# Tracking-Car.net
KiCad netlist of a schematic drawn in EasyEDA Pro
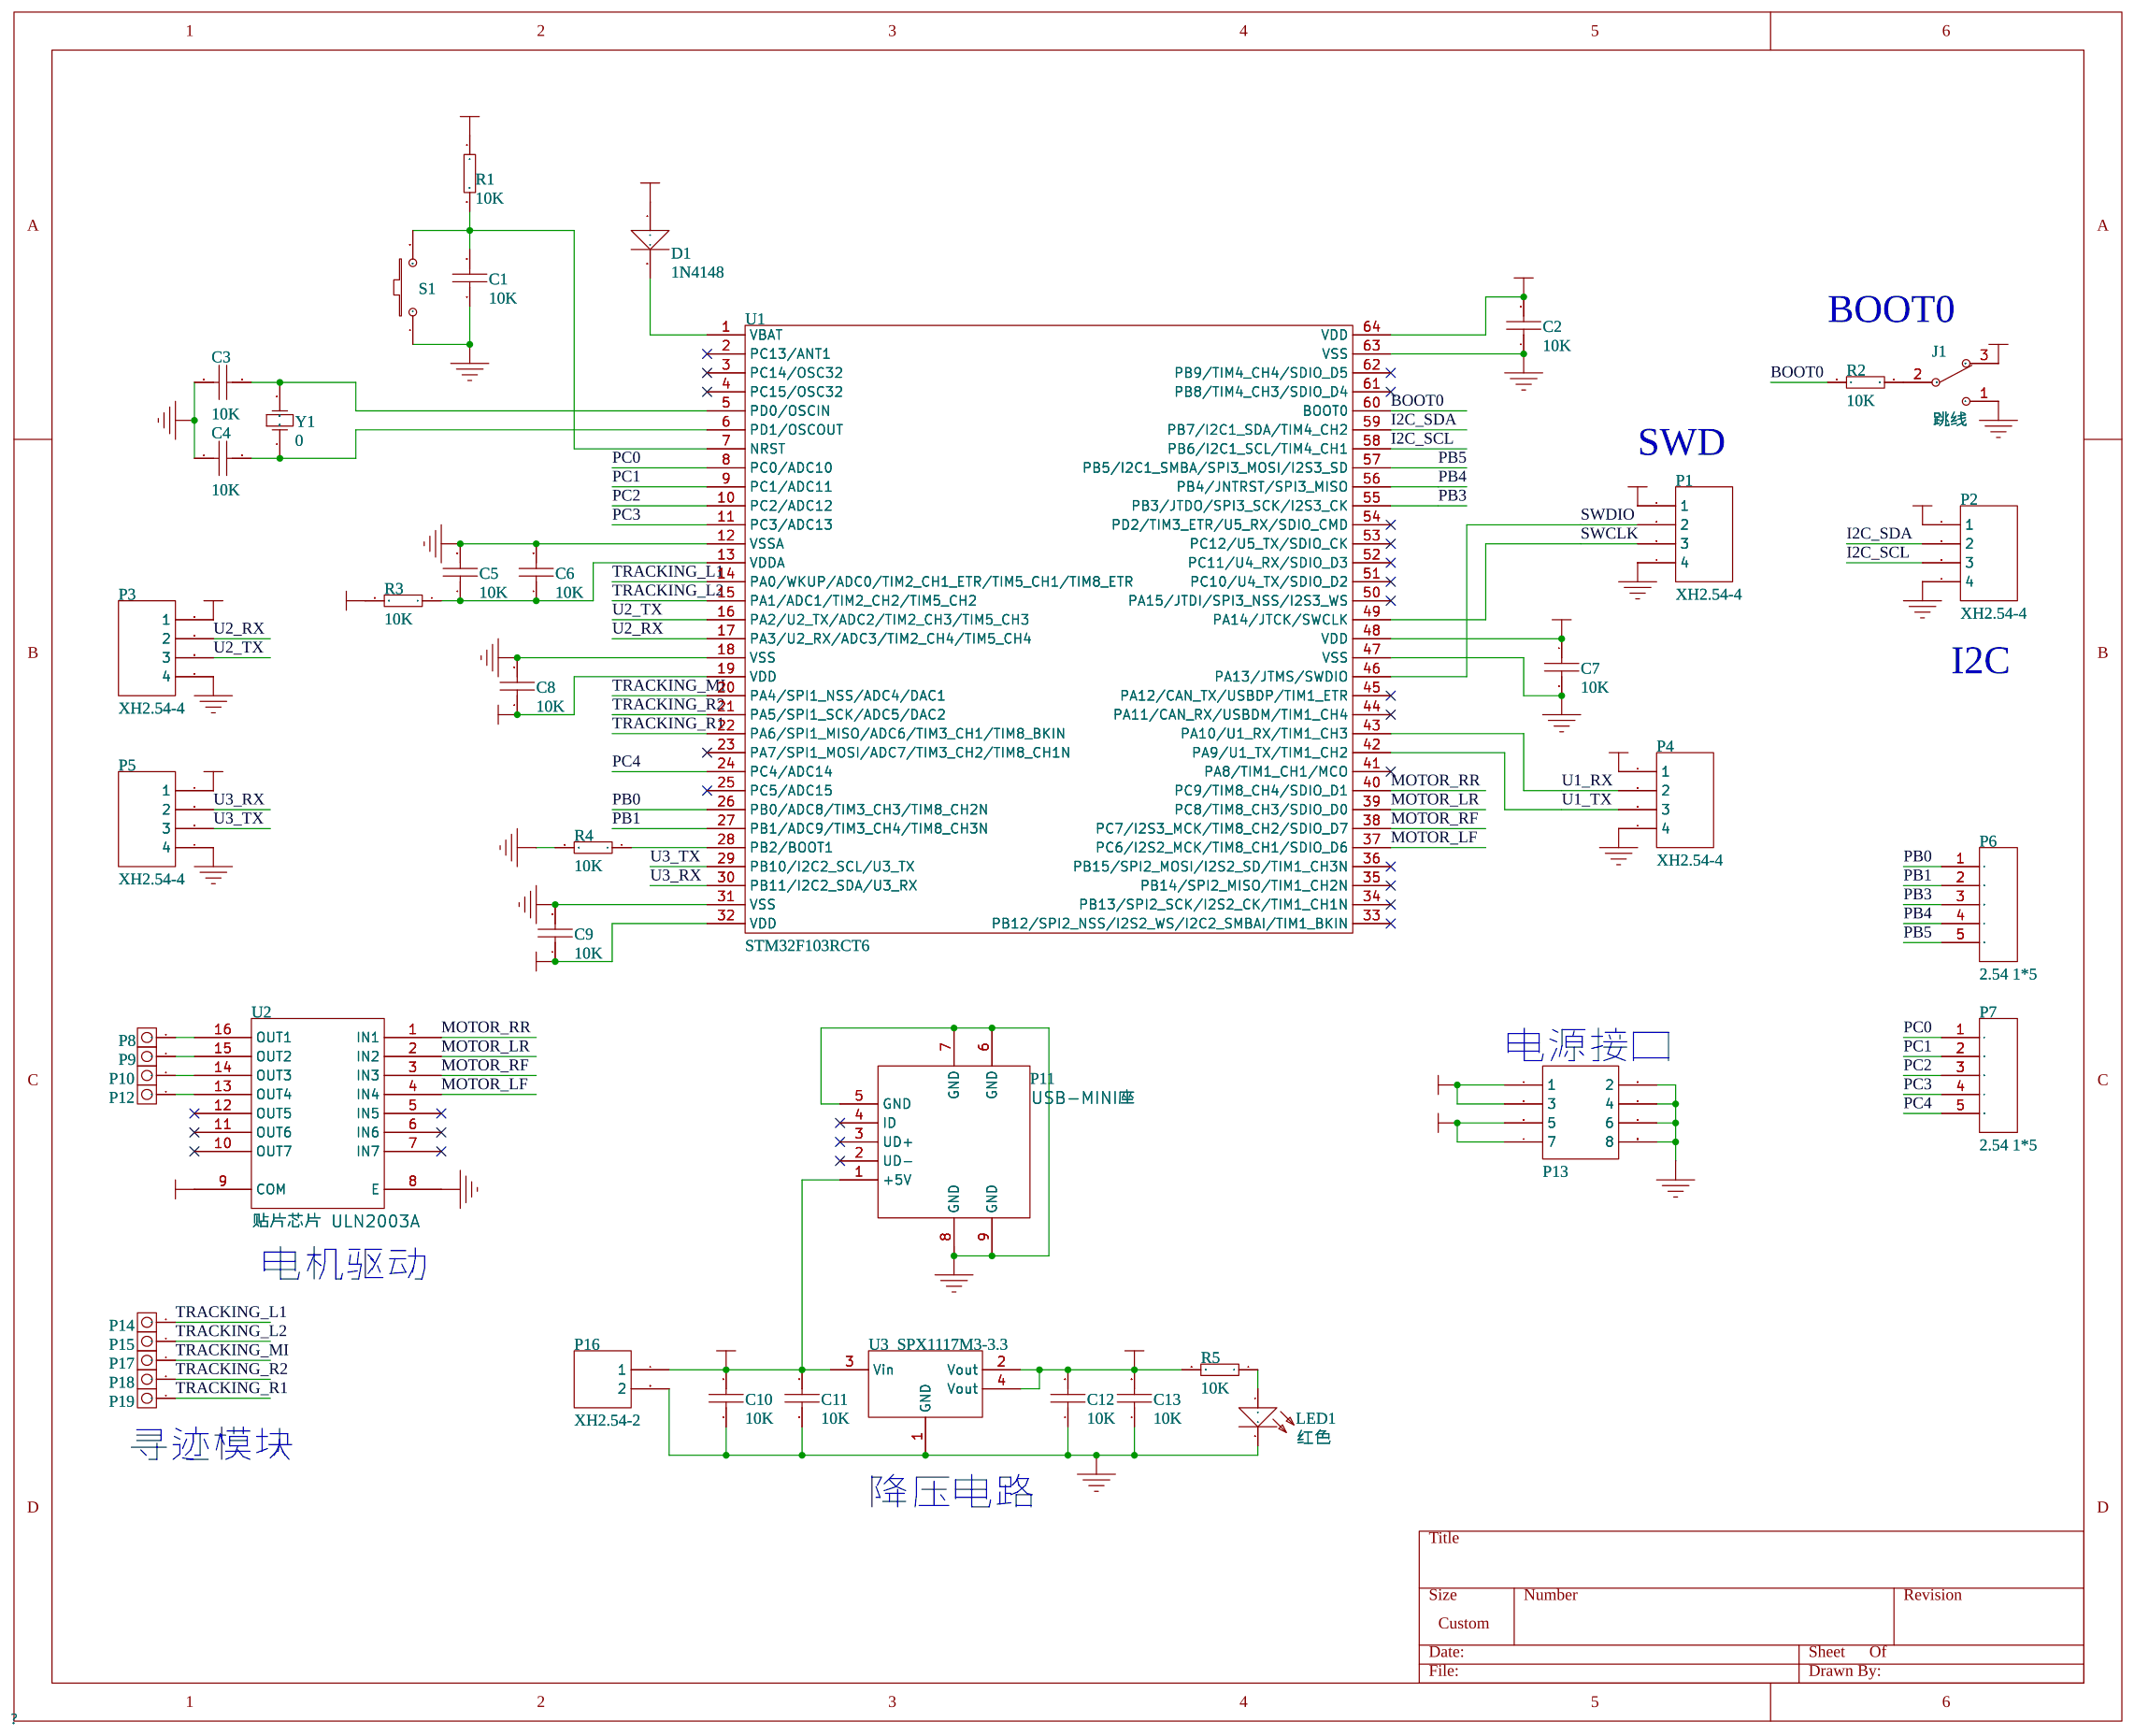
[diagram p0: schematic sheet]

(export (version "E")
  (design (tool "Eeschema 10.0.6"))
  (components
    (comp (ref "C1")
      (value "10K")
      (footprint "easyedapro:0805")
      (libsource (lib "easyedapro") (part "电容 贴片 0805"))
    )
    (comp (ref "C2")
      (value "10K")
      (footprint "easyedapro:0805")
      (libsource (lib "easyedapro") (part "电容 贴片 0805"))
    )
    (comp (ref "C3")
      (value "10K")
      (footprint "easyedapro:0805")
      (libsource (lib "easyedapro") (part "电容 贴片 0805"))
    )
    (comp (ref "C4")
      (value "10K")
      (footprint "easyedapro:0805")
      (libsource (lib "easyedapro") (part "电容 贴片 0805"))
    )
    (comp (ref "C5")
      (value "10K")
      (footprint "easyedapro:0805")
      (libsource (lib "easyedapro") (part "电容 贴片 0805"))
    )
    (comp (ref "C6")
      (value "10K")
      (footprint "easyedapro:0805")
      (libsource (lib "easyedapro") (part "电容 贴片 0805"))
    )
    (comp (ref "C7")
      (value "10K")
      (footprint "easyedapro:0805")
      (libsource (lib "easyedapro") (part "电容 贴片 0805"))
    )
    (comp (ref "C8")
      (value "10K")
      (footprint "easyedapro:0805")
      (libsource (lib "easyedapro") (part "电容 贴片 0805"))
    )
    (comp (ref "C9")
      (value "10K")
      (footprint "easyedapro:0805")
      (libsource (lib "easyedapro") (part "电容 贴片 0805"))
    )
    (comp (ref "C10")
      (value "10K")
      (footprint "easyedapro:0805")
      (libsource (lib "easyedapro") (part "电容 贴片 0805"))
    )
    (comp (ref "C11")
      (value "10K")
      (footprint "easyedapro:0805")
      (libsource (lib "easyedapro") (part "电容 贴片 0805"))
    )
    (comp (ref "C12")
      (value "10K")
      (footprint "easyedapro:0805")
      (libsource (lib "easyedapro") (part "电容 贴片 0805"))
    )
    (comp (ref "C13")
      (value "10K")
      (footprint "easyedapro:0805")
      (libsource (lib "easyedapro") (part "电容 贴片 0805"))
    )
    (comp (ref "D1")
      (value "1N4148")
      (footprint "easyedapro:Ƭ IN4148")
      (libsource (lib "easyedapro") (part "二极管 贴片 1N4148"))
    )
    (comp (ref "J1")
      (value "跳线")
      (footprint "easyedapro:Ų 2.54 1*3")
      (libsource (lib "easyedapro") (part "联结件 跳线端子 2.54-3"))
    )
    (comp (ref "LED1")
      (value "红色")
      (footprint "easyedapro:LED0805")
      (libsource (lib "easyedapro") (part "二极管 贴片发光 0805"))
    )
    (comp (ref "P1")
      (value "XH2.54-4")
      (footprint "easyedapro:VH2.54_4")
      (libsource (lib "easyedapro") (part "联结件 XH2.54-4"))
    )
    (comp (ref "P2")
      (value "XH2.54-4")
      (footprint "easyedapro:VH2.54_4")
      (libsource (lib "easyedapro") (part "联结件 XH2.54-4"))
    )
    (comp (ref "P3")
      (value "XH2.54-4")
      (footprint "easyedapro:VH2.54_4")
      (libsource (lib "easyedapro") (part "联结件 XH2.54-4"))
    )
    (comp (ref "P4")
      (value "XH2.54-4")
      (footprint "easyedapro:VH2.54_4")
      (libsource (lib "easyedapro") (part "联结件 XH2.54-4"))
    )
    (comp (ref "P5")
      (value "XH2.54-4")
      (footprint "easyedapro:VH2.54_4")
      (libsource (lib "easyedapro") (part "联结件 XH2.54-4"))
    )
    (comp (ref "P6")
      (value "2.54 1*5")
      (footprint "easyedapro:Ų 2.54 1*5")
      (libsource (lib "easyedapro") (part "联结件 单排插针 2.54 1*5"))
    )
    (comp (ref "P7")
      (value "2.54 1*5")
      (footprint "easyedapro:Ų 2.54 1*5")
      (libsource (lib "easyedapro") (part "联结件 单排插针 2.54 1*5"))
    )
    (comp (ref "P8")
      (value "DZ254R-11-01-63")
      (fields (field (name "Manufacturer") "DEALON(德艺隆)"))
      (libsource (lib "easyedapro") (part "焊盘"))
    )
    (comp (ref "P9")
      (value "DZ254R-11-01-63")
      (fields (field (name "Manufacturer") "DEALON(德艺隆)"))
      (libsource (lib "easyedapro") (part "焊盘"))
    )
    (comp (ref "P10")
      (value "DZ254R-11-01-63")
      (fields (field (name "Manufacturer") "DEALON(德艺隆)"))
      (libsource (lib "easyedapro") (part "焊盘"))
    )
    (comp (ref "P11")
      (value "USB-MINI座")
      (footprint "easyedapro:USB MINI DIP")
      (libsource (lib "easyedapro") (part "联结件 USB-MINI座"))
    )
    (comp (ref "P12")
      (value "DZ254R-11-01-63")
      (fields (field (name "Manufacturer") "DEALON(德艺隆)"))
      (libsource (lib "easyedapro") (part "焊盘"))
    )
    (comp (ref "P13") (value "双排插针 2.54 2*4") (libsource (lib "easyedapro") (part "联结件 双排插针 2.54 2*4")))
    (comp (ref "P14")
      (value "DZ254R-11-01-63")
      (fields (field (name "Manufacturer") "DEALON(德艺隆)"))
      (libsource (lib "easyedapro") (part "焊盘"))
    )
    (comp (ref "P15")
      (value "DZ254R-11-01-63")
      (fields (field (name "Manufacturer") "DEALON(德艺隆)"))
      (libsource (lib "easyedapro") (part "焊盘"))
    )
    (comp (ref "P16")
      (value "XH2.54-2")
      (footprint "easyedapro:VH2.54_2")
      (libsource (lib "easyedapro") (part "联结件 XH2.54-2"))
    )
    (comp (ref "P17")
      (value "DZ254R-11-01-63")
      (fields (field (name "Manufacturer") "DEALON(德艺隆)"))
      (libsource (lib "easyedapro") (part "焊盘"))
    )
    (comp (ref "P18")
      (value "DZ254R-11-01-63")
      (fields (field (name "Manufacturer") "DEALON(德艺隆)"))
      (libsource (lib "easyedapro") (part "焊盘"))
    )
    (comp (ref "P19")
      (value "DZ254R-11-01-63")
      (fields (field (name "Manufacturer") "DEALON(德艺隆)"))
      (libsource (lib "easyedapro") (part "焊盘"))
    )
    (comp (ref "R1")
      (value "10K")
      (footprint "easyedapro:autoName_08bedda2daa9906a")
      (libsource (lib "easyedapro") (part "电阻 贴片 0805"))
    )
    (comp (ref "R2")
      (value "10K")
      (footprint "easyedapro:autoName_08bedda2daa9906a")
      (libsource (lib "easyedapro") (part "电阻 贴片 0805"))
    )
    (comp (ref "R3")
      (value "10K")
      (footprint "easyedapro:autoName_08bedda2daa9906a")
      (libsource (lib "easyedapro") (part "电阻 贴片 0805"))
    )
    (comp (ref "R4")
      (value "10K")
      (footprint "easyedapro:autoName_08bedda2daa9906a")
      (libsource (lib "easyedapro") (part "电阻 贴片 0805"))
    )
    (comp (ref "R5")
      (value "10K")
      (footprint "easyedapro:autoName_08bedda2daa9906a")
      (libsource (lib "easyedapro") (part "电阻 贴片 0805"))
    )
    (comp (ref "S1")
      (value "key")
      (footprint "easyedapro:ᴥ  6*3")
      (libsource (lib "easyedapro") (part "按键 轻触 3*6"))
    )
    (comp (ref "U1")
      (value "STM32F103RCT6")
      (footprint "easyedapro:LQFP64")
      (description "单片机")
      (libsource (lib "easyedapro") (part "贴片芯片 STM32F103RCT6"))
    )
    (comp (ref "U2")
      (value "贴片芯片 ULN2003A")
      (footprint "easyedapro:SOIC16")
      (libsource (lib "easyedapro") (part "贴片芯片 ULN2003A"))
    )
    (comp (ref "U3")
      (value "SPX1117M3-3.3")
      (footprint "easyedapro:SOT223")
      (description "LDO")
      (libsource (lib "easyedapro") (part "贴片芯片 SPX1117M3-3.3"))
    )
    (comp (ref "Y1")
      (value "0")
      (footprint "easyedapro:BCY-W2/E4.7")
      (libsource (lib "easyedapro") (part "晶振 直插矮"))
    )
  )
  (nets
    (net (code "1") (name "/BOOT0") (class "Default")
      (node (ref "R2") (pin "2") (pinfunction "2_2") (pintype "input"))
      (node (ref "U1") (pin "60") (pinfunction "BOOT0_60") (pintype "input"))
    )
    (net (code "2") (name "/I2C_SCL") (class "Default")
      (node (ref "P2") (pin "3") (pinfunction "3_3") (pintype "input"))
      (node (ref "U1") (pin "58") (pinfunction "PB6/I2C1_SCL/TIM4_CH1_58") (pintype "input"))
    )
    (net (code "3") (name "/I2C_SDA") (class "Default")
      (node (ref "P2") (pin "2") (pinfunction "2_2") (pintype "input"))
      (node (ref "U1") (pin "59") (pinfunction "PB7/I2C1_SDA/TIM4_CH2_59") (pintype "input"))
    )
    (net (code "4") (name "/MOTOR_LF") (class "Default")
      (node (ref "U1") (pin "37") (pinfunction "PC6/I2S2_MCK/TIM8_CH1/SDIO_D6_37") (pintype "input"))
      (node (ref "U2") (pin "4") (pinfunction "IN4_4") (pintype "input"))
    )
    (net (code "5") (name "/MOTOR_LR") (class "Default")
      (node (ref "U1") (pin "39") (pinfunction "PC8/TIM8_CH3/SDIO_D0_39") (pintype "input"))
      (node (ref "U2") (pin "2") (pinfunction "IN2_2") (pintype "input"))
    )
    (net (code "6") (name "/MOTOR_RF") (class "Default")
      (node (ref "U1") (pin "38") (pinfunction "PC7/I2S3_MCK/TIM8_CH2/SDIO_D7_38") (pintype "input"))
      (node (ref "U2") (pin "3") (pinfunction "IN3_3") (pintype "input"))
    )
    (net (code "7") (name "/MOTOR_RR") (class "Default")
      (node (ref "U1") (pin "40") (pinfunction "PC9/TIM8_CH4/SDIO_D1_40") (pintype "input"))
      (node (ref "U2") (pin "1") (pinfunction "IN1_1") (pintype "input"))
    )
    (net (code "8") (name "/PB0") (class "Default")
      (node (ref "P6") (pin "1") (pinfunction "1_1") (pintype "input"))
      (node (ref "U1") (pin "26") (pinfunction "PB0/ADC8/TIM3_CH3/TIM8_CH2N_26") (pintype "input"))
    )
    (net (code "9") (name "/PB1") (class "Default")
      (node (ref "P6") (pin "2") (pinfunction "2_2") (pintype "input"))
      (node (ref "U1") (pin "27") (pinfunction "PB1/ADC9/TIM3_CH4/TIM8_CH3N_27") (pintype "input"))
    )
    (net (code "10") (name "/PB3") (class "Default")
      (node (ref "P6") (pin "3") (pinfunction "3_3") (pintype "input"))
      (node (ref "U1") (pin "55") (pinfunction "PB3/JTDO/SPI3_SCK/I2S3_CK_55") (pintype "input"))
    )
    (net (code "11") (name "/PB4") (class "Default")
      (node (ref "P6") (pin "4") (pinfunction "4_4") (pintype "input"))
      (node (ref "U1") (pin "56") (pinfunction "PB4/JNTRST/SPI3_MISO_56") (pintype "input"))
    )
    (net (code "12") (name "/PB5") (class "Default")
      (node (ref "P6") (pin "5") (pinfunction "5_5") (pintype "input"))
      (node (ref "U1") (pin "57") (pinfunction "PB5/I2C1_SMBA/SPI3_MOSI/I2S3_SD_57") (pintype "input"))
    )
    (net (code "13") (name "/PC0") (class "Default")
      (node (ref "P7") (pin "1") (pinfunction "1_1") (pintype "input"))
      (node (ref "U1") (pin "8") (pinfunction "PC0/ADC10_8") (pintype "input"))
    )
    (net (code "14") (name "/PC1") (class "Default")
      (node (ref "P7") (pin "2") (pinfunction "2_2") (pintype "input"))
      (node (ref "U1") (pin "9") (pinfunction "PC1/ADC11_9") (pintype "input"))
    )
    (net (code "15") (name "/PC2") (class "Default")
      (node (ref "P7") (pin "3") (pinfunction "3_3") (pintype "input"))
      (node (ref "U1") (pin "10") (pinfunction "PC2/ADC12_10") (pintype "input"))
    )
    (net (code "16") (name "/PC3") (class "Default")
      (node (ref "P7") (pin "4") (pinfunction "4_4") (pintype "input"))
      (node (ref "U1") (pin "11") (pinfunction "PC3/ADC13_11") (pintype "input"))
    )
    (net (code "17") (name "/PC4") (class "Default")
      (node (ref "P7") (pin "5") (pinfunction "5_5") (pintype "input"))
      (node (ref "U1") (pin "24") (pinfunction "PC4/ADC14_24") (pintype "input"))
    )
    (net (code "18") (name "/SWCLK") (class "Default")
      (node (ref "P1") (pin "3") (pinfunction "3_3") (pintype "input"))
      (node (ref "U1") (pin "49") (pinfunction "PA14/JTCK/SWCLK_49") (pintype "input"))
    )
    (net (code "19") (name "/SWDIO") (class "Default")
      (node (ref "P1") (pin "2") (pinfunction "2_2") (pintype "input"))
      (node (ref "U1") (pin "46") (pinfunction "PA13/JTMS/SWDIO_46") (pintype "input"))
    )
    (net (code "20") (name "/TRACKING_L1") (class "Default")
      (node (ref "P14") (pin "1") (pinfunction "1_1") (pintype "input"))
      (node (ref "U1") (pin "14") (pinfunction "PA0/WKUP/ADC0/TIM2_CH1_ETR/TIM5_CH1/TIM8_ETR_14") (pintype "input"))
    )
    (net (code "21") (name "/TRACKING_L2") (class "Default")
      (node (ref "P15") (pin "1") (pinfunction "1_1") (pintype "input"))
      (node (ref "U1") (pin "15") (pinfunction "PA1/ADC1/TIM2_CH2/TIM5_CH2_15") (pintype "input"))
    )
    (net (code "22") (name "/TRACKING_MI") (class "Default")
      (node (ref "P17") (pin "1") (pinfunction "1_1") (pintype "input"))
      (node (ref "U1") (pin "20") (pinfunction "PA4/SPI1_NSS/ADC4/DAC1_20") (pintype "input"))
    )
    (net (code "23") (name "/TRACKING_R1") (class "Default")
      (node (ref "P19") (pin "1") (pinfunction "1_1") (pintype "input"))
      (node (ref "U1") (pin "22") (pinfunction "PA6/SPI1_MISO/ADC6/TIM3_CH1/TIM8_BKIN_22") (pintype "input"))
    )
    (net (code "24") (name "/TRACKING_R2") (class "Default")
      (node (ref "P18") (pin "1") (pinfunction "1_1") (pintype "input"))
      (node (ref "U1") (pin "21") (pinfunction "PA5/SPI1_SCK/ADC5/DAC2_21") (pintype "input"))
    )
    (net (code "25") (name "/U1_RX") (class "Default")
      (node (ref "P4") (pin "2") (pinfunction "2_2") (pintype "input"))
      (node (ref "U1") (pin "43") (pinfunction "PA10/U1_RX/TIM1_CH3_43") (pintype "input"))
    )
    (net (code "26") (name "/U1_TX") (class "Default")
      (node (ref "P4") (pin "3") (pinfunction "3_3") (pintype "input"))
      (node (ref "U1") (pin "42") (pinfunction "PA9/U1_TX/TIM1_CH2_42") (pintype "input"))
    )
    (net (code "27") (name "/U2_RX") (class "Default")
      (node (ref "P3") (pin "2") (pinfunction "2_2") (pintype "input"))
      (node (ref "U1") (pin "17") (pinfunction "PA3/U2_RX/ADC3/TIM2_CH4/TIM5_CH4_17") (pintype "input"))
    )
    (net (code "28") (name "/U2_TX") (class "Default")
      (node (ref "P3") (pin "3") (pinfunction "3_3") (pintype "input"))
      (node (ref "U1") (pin "16") (pinfunction "PA2/U2_TX/ADC2/TIM2_CH3/TIM5_CH3_16") (pintype "input"))
    )
    (net (code "29") (name "/U3_RX") (class "Default")
      (node (ref "P5") (pin "2") (pinfunction "2_2") (pintype "input"))
      (node (ref "U1") (pin "30") (pinfunction "PB11/I2C2_SDA/U3_RX_30") (pintype "input"))
    )
    (net (code "30") (name "/U3_TX") (class "Default")
      (node (ref "P5") (pin "3") (pinfunction "3_3") (pintype "input"))
      (node (ref "U1") (pin "29") (pinfunction "PB10/I2C2_SCL/U3_TX_29") (pintype "input"))
    )
    (net (code "31") (name "3.3V") (class "Default")
      (node (ref "C12") (pin "2") (pintype "input"))
      (node (ref "C13") (pin "2") (pintype "input"))
      (node (ref "C2") (pin "2") (pintype "input"))
      (node (ref "C7") (pin "1") (pintype "input"))
      (node (ref "C8") (pin "1") (pintype "input"))
      (node (ref "C9") (pin "1") (pintype "input"))
      (node (ref "D1") (pin "1") (pinfunction "A_1") (pintype "input"))
      (node (ref "J1") (pin "3") (pinfunction "3_3") (pintype "input"))
      (node (ref "P1") (pin "1") (pinfunction "1_1") (pintype "input"))
      (node (ref "P13") (pin "1") (pinfunction "1_1") (pintype "input"))
      (node (ref "P13") (pin "3") (pinfunction "3_3") (pintype "input"))
      (node (ref "P2") (pin "1") (pinfunction "1_1") (pintype "input"))
      (node (ref "P3") (pin "1") (pinfunction "1_1") (pintype "input"))
      (node (ref "P4") (pin "1") (pinfunction "1_1") (pintype "input"))
      (node (ref "P5") (pin "1") (pinfunction "1_1") (pintype "input"))
      (node (ref "R1") (pin "1") (pinfunction "1_1") (pintype "input"))
      (node (ref "R3") (pin "2") (pinfunction "2_2") (pintype "input"))
      (node (ref "R5") (pin "2") (pinfunction "2_2") (pintype "input"))
      (node (ref "U1") (pin "19") (pinfunction "VDD_19") (pintype "input"))
      (node (ref "U1") (pin "32") (pinfunction "VDD_32") (pintype "input"))
      (node (ref "U1") (pin "48") (pinfunction "VDD_48") (pintype "input"))
      (node (ref "U1") (pin "64") (pinfunction "VDD_64") (pintype "input"))
      (node (ref "U3") (pin "2") (pinfunction "Vout_2") (pintype "input"))
      (node (ref "U3") (pin "4") (pinfunction "Vout_4") (pintype "input"))
    )
    (net (code "32") (name "5V") (class "Default")
      (node (ref "C10") (pin "2") (pintype "input"))
      (node (ref "C11") (pin "2") (pintype "input"))
      (node (ref "P11") (pin "1") (pinfunction "+5V_1") (pintype "input"))
      (node (ref "P13") (pin "5") (pinfunction "5_5") (pintype "input"))
      (node (ref "P13") (pin "7") (pinfunction "7_7") (pintype "input"))
      (node (ref "P16") (pin "1") (pinfunction "1_1") (pintype "input"))
      (node (ref "U2") (pin "9") (pinfunction "COM_9") (pintype "input"))
      (node (ref "U3") (pin "3") (pinfunction "Vin_3") (pintype "input"))
    )
    (net (code "33") (name "GND") (class "Default")
      (node (ref "C1") (pin "1") (pintype "input"))
      (node (ref "C10") (pin "1") (pintype "input"))
      (node (ref "C11") (pin "1") (pintype "input"))
      (node (ref "C12") (pin "1") (pintype "input"))
      (node (ref "C13") (pin "1") (pintype "input"))
      (node (ref "C2") (pin "1") (pintype "input"))
      (node (ref "C3") (pin "1") (pintype "input"))
      (node (ref "C4") (pin "1") (pintype "input"))
      (node (ref "C5") (pin "2") (pintype "input"))
      (node (ref "C6") (pin "2") (pintype "input"))
      (node (ref "C7") (pin "2") (pintype "input"))
      (node (ref "C8") (pin "2") (pintype "input"))
      (node (ref "C9") (pin "2") (pintype "input"))
      (node (ref "J1") (pin "1") (pinfunction "1_1") (pintype "input"))
      (node (ref "LED1") (pin "2") (pinfunction "K_2") (pintype "input"))
      (node (ref "P1") (pin "4") (pinfunction "4_4") (pintype "input"))
      (node (ref "P11") (pin "5") (pinfunction "GND_5") (pintype "input"))
      (node (ref "P11") (pin "6") (pinfunction "GND_6") (pintype "input"))
      (node (ref "P11") (pin "7") (pinfunction "GND_7") (pintype "input"))
      (node (ref "P11") (pin "8") (pinfunction "GND_8") (pintype "input"))
      (node (ref "P11") (pin "9") (pinfunction "GND_9") (pintype "input"))
      (node (ref "P13") (pin "2") (pinfunction "2_2") (pintype "input"))
      (node (ref "P13") (pin "4") (pinfunction "4_4") (pintype "input"))
      (node (ref "P13") (pin "6") (pinfunction "6_6") (pintype "input"))
      (node (ref "P13") (pin "8") (pinfunction "8_8") (pintype "input"))
      (node (ref "P16") (pin "2") (pinfunction "2_2") (pintype "input"))
      (node (ref "P2") (pin "4") (pinfunction "4_4") (pintype "input"))
      (node (ref "P3") (pin "4") (pinfunction "4_4") (pintype "input"))
      (node (ref "P4") (pin "4") (pinfunction "4_4") (pintype "input"))
      (node (ref "P5") (pin "4") (pinfunction "4_4") (pintype "input"))
      (node (ref "R4") (pin "2") (pinfunction "2_2") (pintype "input"))
      (node (ref "S1") (pin "1") (pinfunction "1_1") (pintype "input"))
      (node (ref "U1") (pin "12") (pinfunction "VSSA_12") (pintype "input"))
      (node (ref "U1") (pin "18") (pinfunction "VSS_18") (pintype "input"))
      (node (ref "U1") (pin "31") (pinfunction "VSS_31") (pintype "input"))
      (node (ref "U1") (pin "47") (pinfunction "VSS_47") (pintype "input"))
      (node (ref "U1") (pin "63") (pinfunction "VSS_63") (pintype "input"))
      (node (ref "U2") (pin "8") (pinfunction "E_8") (pintype "input"))
      (node (ref "U3") (pin "1") (pinfunction "GND_1") (pintype "input"))
    )
    (net (code "34") (name "Net-(D1-K)") (class "Default")
      (node (ref "D1") (pin "2") (pinfunction "K_2") (pintype "input"))
      (node (ref "U1") (pin "1") (pinfunction "VBAT_1") (pintype "input"))
    )
    (net (code "35") (name "Net-(J1-Pad2)") (class "Default")
      (node (ref "J1") (pin "2") (pinfunction "2_2") (pintype "input"))
      (node (ref "R2") (pin "1") (pinfunction "1_1") (pintype "input"))
    )
    (net (code "36") (name "Net-(LED1-A)") (class "Default")
      (node (ref "LED1") (pin "1") (pinfunction "A_1") (pintype "input"))
      (node (ref "R5") (pin "1") (pinfunction "1_1") (pintype "input"))
    )
    (net (code "37") (name "Net-(U1-NRST)") (class "Default")
      (node (ref "C1") (pin "2") (pintype "input"))
      (node (ref "R1") (pin "2") (pinfunction "2_2") (pintype "input"))
      (node (ref "S1") (pin "2") (pinfunction "2_2") (pintype "input"))
      (node (ref "U1") (pin "7") (pinfunction "NRST_7") (pintype "input"))
    )
    (net (code "38") (name "Net-(U1-PB2{slash}BOOT1)") (class "Default")
      (node (ref "R4") (pin "1") (pinfunction "1_1") (pintype "input"))
      (node (ref "U1") (pin "28") (pinfunction "PB2/BOOT1_28") (pintype "input"))
    )
    (net (code "39") (name "Net-(U1-PD0{slash}OSCIN)") (class "Default")
      (node (ref "C3") (pin "2") (pintype "input"))
      (node (ref "U1") (pin "5") (pinfunction "PD0/OSCIN_5") (pintype "input"))
      (node (ref "Y1") (pin "2") (pinfunction "OSC2_2") (pintype "input"))
    )
    (net (code "40") (name "Net-(U1-PD1{slash}OSCOUT)") (class "Default")
      (node (ref "C4") (pin "2") (pintype "input"))
      (node (ref "U1") (pin "6") (pinfunction "PD1/OSCOUT_6") (pintype "input"))
      (node (ref "Y1") (pin "1") (pinfunction "OSC1_1") (pintype "input"))
    )
    (net (code "41") (name "Net-(U1-VDDA)") (class "Default")
      (node (ref "C5") (pin "1") (pintype "input"))
      (node (ref "C6") (pin "1") (pintype "input"))
      (node (ref "R3") (pin "1") (pinfunction "1_1") (pintype "input"))
      (node (ref "U1") (pin "13") (pinfunction "VDDA_13") (pintype "input"))
    )
    (net (code "42") (name "Net-(U2-OUT1)") (class "Default")
      (node (ref "P8") (pin "1") (pinfunction "1_1") (pintype "input"))
      (node (ref "U2") (pin "16") (pinfunction "OUT1_16") (pintype "input"))
    )
    (net (code "43") (name "Net-(U2-OUT2)") (class "Default")
      (node (ref "P9") (pin "1") (pinfunction "1_1") (pintype "input"))
      (node (ref "U2") (pin "15") (pinfunction "OUT2_15") (pintype "input"))
    )
    (net (code "44") (name "Net-(U2-OUT3)") (class "Default")
      (node (ref "P10") (pin "1") (pinfunction "1_1") (pintype "input"))
      (node (ref "U2") (pin "14") (pinfunction "OUT3_14") (pintype "input"))
    )
    (net (code "45") (name "Net-(U2-OUT4)") (class "Default")
      (node (ref "P12") (pin "1") (pinfunction "1_1") (pintype "input"))
      (node (ref "U2") (pin "13") (pinfunction "OUT4_13") (pintype "input"))
    )
    (net (code "46") (name "unconnected-(P11-ID-Pad4)") (class "Default")
      (node (ref "P11") (pin "4") (pinfunction "ID_4") (pintype "input+no_connect"))
    )
    (net (code "47") (name "unconnected-(P11-UD+-Pad3)") (class "Default")
      (node (ref "P11") (pin "3") (pinfunction "UD+_3") (pintype "input+no_connect"))
    )
    (net (code "48") (name "unconnected-(P11-UD--Pad2)") (class "Default")
      (node (ref "P11") (pin "2") (pinfunction "UD-_2") (pintype "input+no_connect"))
    )
    (net (code "49") (name "unconnected-(U1-PA7{slash}SPI1_MOSI{slash}ADC7{slash}TIM3_CH2{slash}TIM8_CH1N-Pad23)") (class "Default")
      (node (ref "U1") (pin "23") (pinfunction "PA7/SPI1_MOSI/ADC7/TIM3_CH2/TIM8_CH1N_23") (pintype "input+no_connect"))
    )
    (net (code "50") (name "unconnected-(U1-PA8{slash}TIM1_CH1{slash}MCO-Pad41)") (class "Default")
      (node (ref "U1") (pin "41") (pinfunction "PA8/TIM1_CH1/MCO_41") (pintype "input+no_connect"))
    )
    (net (code "51") (name "unconnected-(U1-PA11{slash}CAN_RX{slash}USBDM{slash}TIM1_CH4-Pad44)") (class "Default")
      (node (ref "U1") (pin "44") (pinfunction "PA11/CAN_RX/USBDM/TIM1_CH4_44") (pintype "input+no_connect"))
    )
    (net (code "52") (name "unconnected-(U1-PA12{slash}CAN_TX{slash}USBDP{slash}TIM1_ETR-Pad45)") (class "Default")
      (node (ref "U1") (pin "45") (pinfunction "PA12/CAN_TX/USBDP/TIM1_ETR_45") (pintype "input+no_connect"))
    )
    (net (code "53") (name "unconnected-(U1-PA15{slash}JTDI{slash}SPI3_NSS{slash}I2S3_WS-Pad50)") (class "Default")
      (node (ref "U1") (pin "50") (pinfunction "PA15/JTDI/SPI3_NSS/I2S3_WS_50") (pintype "input+no_connect"))
    )
    (net (code "54") (name "unconnected-(U1-PB8{slash}TIM4_CH3{slash}SDIO_D4-Pad61)") (class "Default")
      (node (ref "U1") (pin "61") (pinfunction "PB8/TIM4_CH3/SDIO_D4_61") (pintype "input+no_connect"))
    )
    (net (code "55") (name "unconnected-(U1-PB9{slash}TIM4_CH4{slash}SDIO_D5-Pad62)") (class "Default")
      (node (ref "U1") (pin "62") (pinfunction "PB9/TIM4_CH4/SDIO_D5_62") (pintype "input+no_connect"))
    )
    (net (code "56") (name "unconnected-(U1-PB12{slash}SPI2_NSS{slash}I2S2_WS{slash}I2C2_SMBAI{slash}TIM1_BKIN-Pad33)") (class "Default")
      (node (ref "U1") (pin "33") (pinfunction "PB12/SPI2_NSS/I2S2_WS/I2C2_SMBAI/TIM1_BKIN_33") (pintype "input+no_connect"))
    )
    (net (code "57") (name "unconnected-(U1-PB13{slash}SPI2_SCK{slash}I2S2_CK{slash}TIM1_CH1N-Pad34)") (class "Default")
      (node (ref "U1") (pin "34") (pinfunction "PB13/SPI2_SCK/I2S2_CK/TIM1_CH1N_34") (pintype "input+no_connect"))
    )
    (net (code "58") (name "unconnected-(U1-PB14{slash}SPI2_MISO{slash}TIM1_CH2N-Pad35)") (class "Default")
      (node (ref "U1") (pin "35") (pinfunction "PB14/SPI2_MISO/TIM1_CH2N_35") (pintype "input+no_connect"))
    )
    (net (code "59") (name "unconnected-(U1-PB15{slash}SPI2_MOSI{slash}I2S2_SD{slash}TIM1_CH3N-Pad36)") (class "Default")
      (node (ref "U1") (pin "36") (pinfunction "PB15/SPI2_MOSI/I2S2_SD/TIM1_CH3N_36") (pintype "input+no_connect"))
    )
    (net (code "60") (name "unconnected-(U1-PC5{slash}ADC15-Pad25)") (class "Default")
      (node (ref "U1") (pin "25") (pinfunction "PC5/ADC15_25") (pintype "input+no_connect"))
    )
    (net (code "61") (name "unconnected-(U1-PC10{slash}U4_TX{slash}SDIO_D2-Pad51)") (class "Default")
      (node (ref "U1") (pin "51") (pinfunction "PC10/U4_TX/SDIO_D2_51") (pintype "input+no_connect"))
    )
    (net (code "62") (name "unconnected-(U1-PC11{slash}U4_RX{slash}SDIO_D3-Pad52)") (class "Default")
      (node (ref "U1") (pin "52") (pinfunction "PC11/U4_RX/SDIO_D3_52") (pintype "input+no_connect"))
    )
    (net (code "63") (name "unconnected-(U1-PC12{slash}U5_TX{slash}SDIO_CK-Pad53)") (class "Default")
      (node (ref "U1") (pin "53") (pinfunction "PC12/U5_TX/SDIO_CK_53") (pintype "input+no_connect"))
    )
    (net (code "64") (name "unconnected-(U1-PC13{slash}ANT1-Pad2)") (class "Default")
      (node (ref "U1") (pin "2") (pinfunction "PC13/ANT1_2") (pintype "input+no_connect"))
    )
    (net (code "65") (name "unconnected-(U1-PC14{slash}OSC32-Pad3)") (class "Default")
      (node (ref "U1") (pin "3") (pinfunction "PC14/OSC32_3") (pintype "input+no_connect"))
    )
    (net (code "66") (name "unconnected-(U1-PC15{slash}OSC32-Pad4)") (class "Default")
      (node (ref "U1") (pin "4") (pinfunction "PC15/OSC32_4") (pintype "input+no_connect"))
    )
    (net (code "67") (name "unconnected-(U1-PD2{slash}TIM3_ETR{slash}U5_RX{slash}SDIO_CMD-Pad54)") (class "Default")
      (node (ref "U1") (pin "54") (pinfunction "PD2/TIM3_ETR/U5_RX/SDIO_CMD_54") (pintype "input+no_connect"))
    )
    (net (code "68") (name "unconnected-(U2-IN5-Pad5)") (class "Default")
      (node (ref "U2") (pin "5") (pinfunction "IN5_5") (pintype "input+no_connect"))
    )
    (net (code "69") (name "unconnected-(U2-IN6-Pad6)") (class "Default")
      (node (ref "U2") (pin "6") (pinfunction "IN6_6") (pintype "input+no_connect"))
    )
    (net (code "70") (name "unconnected-(U2-IN7-Pad7)") (class "Default")
      (node (ref "U2") (pin "7") (pinfunction "IN7_7") (pintype "input+no_connect"))
    )
    (net (code "71") (name "unconnected-(U2-OUT5-Pad12)") (class "Default")
      (node (ref "U2") (pin "12") (pinfunction "OUT5_12") (pintype "input+no_connect"))
    )
    (net (code "72") (name "unconnected-(U2-OUT6-Pad11)") (class "Default")
      (node (ref "U2") (pin "11") (pinfunction "OUT6_11") (pintype "input+no_connect"))
    )
    (net (code "73") (name "unconnected-(U2-OUT7-Pad10)") (class "Default")
      (node (ref "U2") (pin "10") (pinfunction "OUT7_10") (pintype "input+no_connect"))
    )
  )
)
